# placaESP-AC_LAR_01.net
KiCad netlist of a schematic drawn in EAGLE
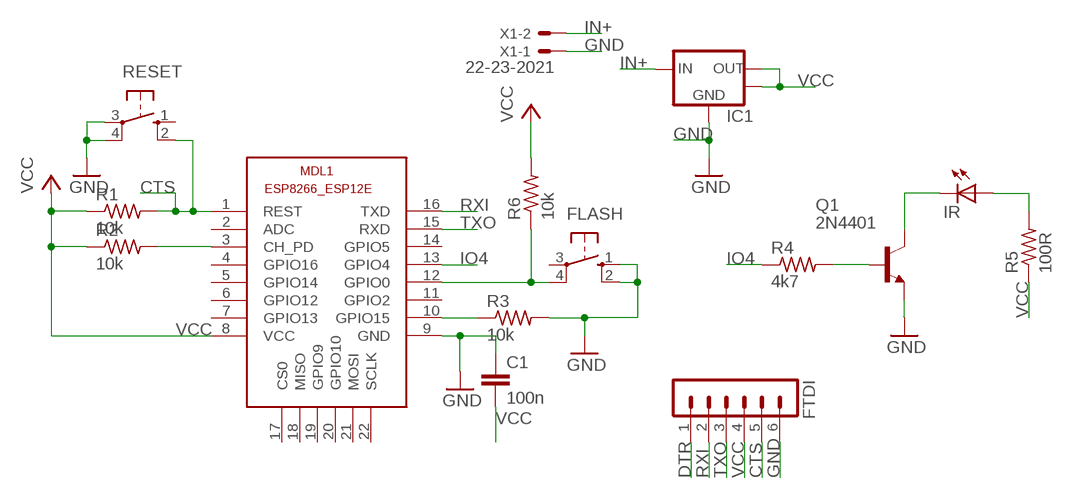
[diagram p0: schematic, sheet 1]

(export (version "E")
  (design (tool "Eeschema 10.0.6"))
  (components
    (comp (ref "C1")
      (value "100n")
      (footprint "eagle-import:C025-025X050")
      (libsource (lib "eagle-import") (part "C-EU025-025X050"))
    )
    (comp (ref "FLASH")
      (value "10-XX")
      (footprint "eagle-import:B3F-10XX")
      (fields (field (name "MPN") "B3F-1000"))
      (libsource (lib "eagle-import") (part "10-XX"))
    )
    (comp (ref "FTDI")
      (value "MA06-1")
      (footprint "eagle-import:MA06-1")
      (libsource (lib "eagle-import") (part "MA06-1"))
    )
    (comp (ref "IC1")
      (value "AMS1117")
      (footprint "eagle-import:AMS1117")
      (libsource (lib "eagle-import") (part "AMS1117"))
    )
    (comp (ref "IR")
      (value "SFH482")
      (footprint "eagle-import:SFH482")
      (libsource (lib "eagle-import") (part "SFH482"))
    )
    (comp (ref "MDL1")
      (value "ESP8266-12EESP8266-ESP12E")
      (footprint "eagle-import:ESP8266-ESP12E")
      (libsource (lib "eagle-import") (part "ESP8266-12EESP8266-ESP12E"))
    )
    (comp (ref "Q1")
      (value "2N4401")
      (footprint "eagle-import:TO92")
      (libsource (lib "eagle-import") (part "2N4416"))
    )
    (comp (ref "R1")
      (value "10k")
      (footprint "eagle-import:0207_10")
      (libsource (lib "eagle-import") (part "R-US_0207/10"))
    )
    (comp (ref "R2")
      (value "10k")
      (footprint "eagle-import:0207_10")
      (libsource (lib "eagle-import") (part "R-US_0207/10"))
    )
    (comp (ref "R3")
      (value "10k")
      (footprint "eagle-import:0207_10")
      (libsource (lib "eagle-import") (part "R-US_0207/10"))
    )
    (comp (ref "R4")
      (value "4k7")
      (footprint "eagle-import:0207_10")
      (libsource (lib "eagle-import") (part "R-US_0207/10"))
    )
    (comp (ref "R5")
      (value "100R")
      (footprint "eagle-import:0207_10")
      (libsource (lib "eagle-import") (part "R-US_0207/10"))
    )
    (comp (ref "R6")
      (value "10k")
      (footprint "eagle-import:0207_10")
      (libsource (lib "eagle-import") (part "R-US_0207/10"))
    )
    (comp (ref "RESET")
      (value "10-XX")
      (footprint "eagle-import:B3F-10XX")
      (fields (field (name "MPN") "B3F-1000"))
      (libsource (lib "eagle-import") (part "10-XX"))
    )
    (comp (ref "X1")
      (value "22-23-2021")
      (footprint "eagle-import:22-23-2021")
      (fields (field (name "MF") "MOLEX"))
      (libsource (lib "eagle-import") (part "22-23-2021"))
    )
  )
  (nets
    (net (code "1") (name "/CTS") (class "Default")
      (node (ref "FTDI") (pin "5") (pinfunction "5_5") (pintype "passive"))
      (node (ref "MDL1") (pin "1") (pinfunction "REST_1") (pintype "bidirectional"))
      (node (ref "R1") (pin "2") (pinfunction "2_2") (pintype "passive"))
      (node (ref "RESET") (pin "2") (pinfunction "S1_2") (pintype "passive"))
    )
    (net (code "2") (name "/DTR") (class "Default")
      (node (ref "FTDI") (pin "1") (pinfunction "1_1") (pintype "passive"))
    )
    (net (code "3") (name "/IN+") (class "Default")
      (node (ref "IC1") (pin "VIN") (pinfunction "VIN_VIN") (pintype "input"))
      (node (ref "X1") (pin "2") (pinfunction "S_2") (pintype "passive"))
    )
    (net (code "4") (name "/IO4") (class "Default")
      (node (ref "MDL1") (pin "13") (pinfunction "GPIO4_13") (pintype "bidirectional"))
      (node (ref "R4") (pin "1") (pinfunction "1_1") (pintype "passive"))
    )
    (net (code "5") (name "/RXI") (class "Default")
      (node (ref "FTDI") (pin "2") (pinfunction "2_2") (pintype "passive"))
      (node (ref "MDL1") (pin "16") (pinfunction "TXD_16") (pintype "bidirectional"))
    )
    (net (code "6") (name "/TXO") (class "Default")
      (node (ref "FTDI") (pin "3") (pinfunction "3_3") (pintype "passive"))
      (node (ref "MDL1") (pin "15") (pinfunction "RXD_15") (pintype "bidirectional"))
    )
    (net (code "7") (name "GND") (class "Default")
      (node (ref "C1") (pin "1") (pinfunction "1_1") (pintype "passive"))
      (node (ref "FLASH") (pin "1") (pinfunction "S_1") (pintype "passive"))
      (node (ref "FLASH") (pin "2") (pinfunction "S1_2") (pintype "passive"))
      (node (ref "FTDI") (pin "6") (pinfunction "6_6") (pintype "passive"))
      (node (ref "IC1") (pin "GND") (pinfunction "ADJ-GND_GND") (pintype "power_in"))
      (node (ref "MDL1") (pin "9") (pinfunction "GND_9") (pintype "bidirectional"))
      (node (ref "Q1") (pin "3") (pinfunction "E_3") (pintype "passive"))
      (node (ref "R3") (pin "2") (pinfunction "2_2") (pintype "passive"))
      (node (ref "RESET") (pin "3") (pinfunction "P_3") (pintype "passive"))
      (node (ref "RESET") (pin "4") (pinfunction "P1_4") (pintype "passive"))
      (node (ref "X1") (pin "1") (pinfunction "S_1") (pintype "passive"))
    )
    (net (code "8") (name "Net-(FLASH-P1)") (class "Default")
      (node (ref "FLASH") (pin "4") (pinfunction "P1_4") (pintype "passive"))
      (node (ref "MDL1") (pin "12") (pinfunction "GPIO0_12") (pintype "bidirectional"))
      (node (ref "R6") (pin "1") (pinfunction "1_1") (pintype "passive"))
    )
    (net (code "9") (name "Net-(IR-C)") (class "Default")
      (node (ref "IR") (pin "K") (pinfunction "C_K") (pintype "passive"))
      (node (ref "Q1") (pin "1") (pinfunction "C_1") (pintype "passive"))
    )
    (net (code "10") (name "Net-(IR-PadA)") (class "Default")
      (node (ref "IR") (pin "A") (pinfunction "A_A") (pintype "passive"))
      (node (ref "R5") (pin "2") (pinfunction "2_2") (pintype "passive"))
    )
    (net (code "11") (name "Net-(MDL1-CH_PD)") (class "Default")
      (node (ref "MDL1") (pin "3") (pinfunction "CH_PD_3") (pintype "bidirectional"))
      (node (ref "R2") (pin "2") (pinfunction "2_2") (pintype "passive"))
    )
    (net (code "12") (name "Net-(MDL1-GPIO15)") (class "Default")
      (node (ref "MDL1") (pin "10") (pinfunction "GPIO15_10") (pintype "bidirectional"))
      (node (ref "R3") (pin "1") (pinfunction "1_1") (pintype "passive"))
    )
    (net (code "13") (name "Net-(Q1-B)") (class "Default")
      (node (ref "Q1") (pin "2") (pinfunction "B_2") (pintype "passive"))
      (node (ref "R4") (pin "2") (pinfunction "2_2") (pintype "passive"))
    )
    (net (code "14") (name "VCC") (class "Default")
      (node (ref "C1") (pin "2") (pinfunction "2_2") (pintype "passive"))
      (node (ref "FTDI") (pin "4") (pinfunction "4_4") (pintype "passive"))
      (node (ref "IC1") (pin "HEATSINK") (pinfunction "HEATSINK_HEATSINK") (pintype "power_in"))
      (node (ref "IC1") (pin "VOUT") (pinfunction "VOUT_VOUT") (pintype "power_in"))
      (node (ref "MDL1") (pin "8") (pinfunction "VCC_8") (pintype "bidirectional"))
      (node (ref "R1") (pin "1") (pinfunction "1_1") (pintype "passive"))
      (node (ref "R2") (pin "1") (pinfunction "1_1") (pintype "passive"))
      (node (ref "R5") (pin "1") (pinfunction "1_1") (pintype "passive"))
      (node (ref "R6") (pin "2") (pinfunction "2_2") (pintype "passive"))
    )
    (net (code "15") (name "unconnected-(FLASH-P-Pad3)") (class "Default")
      (node (ref "FLASH") (pin "3") (pinfunction "P_3") (pintype "passive"))
    )
    (net (code "16") (name "unconnected-(MDL1-ADC-Pad2)") (class "Default")
      (node (ref "MDL1") (pin "2") (pinfunction "ADC_2") (pintype "bidirectional"))
    )
    (net (code "17") (name "unconnected-(MDL1-CS0-Pad17)") (class "Default")
      (node (ref "MDL1") (pin "17") (pinfunction "CS0_17") (pintype "bidirectional"))
    )
    (net (code "18") (name "unconnected-(MDL1-GPIO2-Pad11)") (class "Default")
      (node (ref "MDL1") (pin "11") (pinfunction "GPIO2_11") (pintype "bidirectional"))
    )
    (net (code "19") (name "unconnected-(MDL1-GPIO5-Pad14)") (class "Default")
      (node (ref "MDL1") (pin "14") (pinfunction "GPIO5_14") (pintype "bidirectional"))
    )
    (net (code "20") (name "unconnected-(MDL1-GPIO9-Pad19)") (class "Default")
      (node (ref "MDL1") (pin "19") (pinfunction "GPIO9_19") (pintype "bidirectional"))
    )
    (net (code "21") (name "unconnected-(MDL1-GPIO10-Pad20)") (class "Default")
      (node (ref "MDL1") (pin "20") (pinfunction "GPIO10_20") (pintype "bidirectional"))
    )
    (net (code "22") (name "unconnected-(MDL1-GPIO12-Pad6)") (class "Default")
      (node (ref "MDL1") (pin "6") (pinfunction "GPIO12_6") (pintype "bidirectional"))
    )
    (net (code "23") (name "unconnected-(MDL1-GPIO13-Pad7)") (class "Default")
      (node (ref "MDL1") (pin "7") (pinfunction "GPIO13_7") (pintype "bidirectional"))
    )
    (net (code "24") (name "unconnected-(MDL1-GPIO14-Pad5)") (class "Default")
      (node (ref "MDL1") (pin "5") (pinfunction "GPIO14_5") (pintype "bidirectional"))
    )
    (net (code "25") (name "unconnected-(MDL1-GPIO16-Pad4)") (class "Default")
      (node (ref "MDL1") (pin "4") (pinfunction "GPIO16_4") (pintype "bidirectional"))
    )
    (net (code "26") (name "unconnected-(MDL1-MISO-Pad18)") (class "Default")
      (node (ref "MDL1") (pin "18") (pinfunction "MISO_18") (pintype "bidirectional"))
    )
    (net (code "27") (name "unconnected-(MDL1-MOSI-Pad21)") (class "Default")
      (node (ref "MDL1") (pin "21") (pinfunction "MOSI_21") (pintype "bidirectional"))
    )
    (net (code "28") (name "unconnected-(MDL1-SCLK-Pad22)") (class "Default")
      (node (ref "MDL1") (pin "22") (pinfunction "SCLK_22") (pintype "bidirectional"))
    )
    (net (code "29") (name "unconnected-(RESET-S-Pad1)") (class "Default")
      (node (ref "RESET") (pin "1") (pinfunction "S_1") (pintype "passive"))
    )
  )
)
